# t1-power.net
KiCad netlist of a schematic drawn in Altium Designer
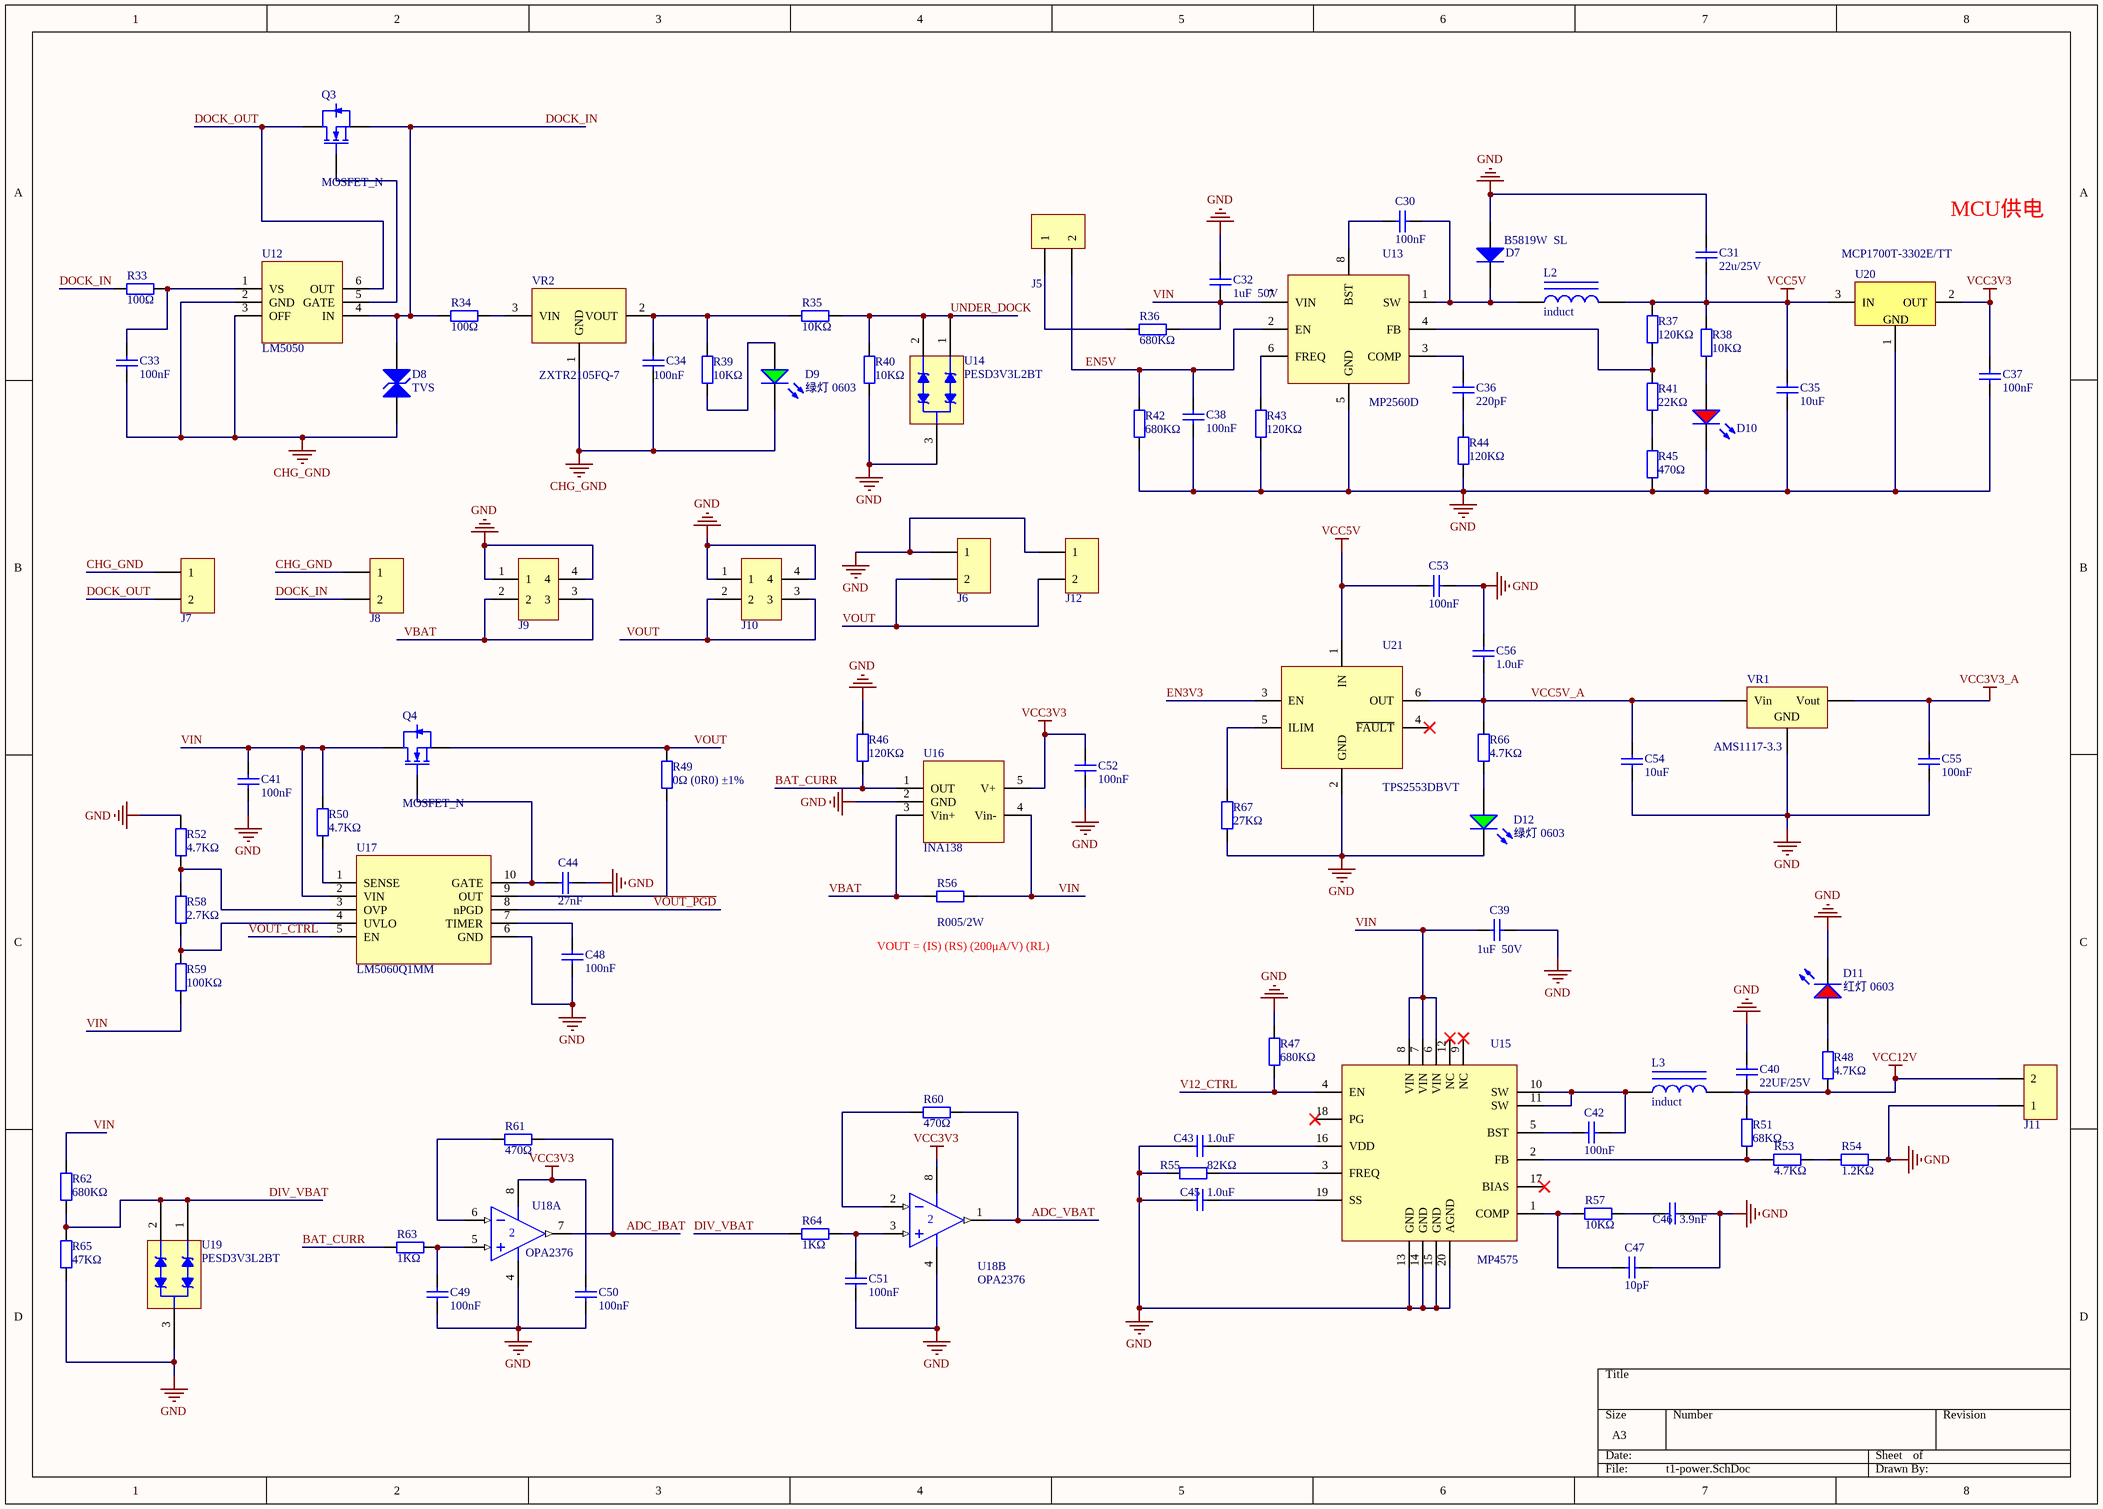
[diagram p0: t1-power.SchDoc]

(export (version "E")
  (design (tool "Eeschema 10.0.6"))
  (components
    (comp (ref "C30")
      (value "100nF")
      (footprint "0402_C")
      (description "贴片电容")
      (libsource (lib "AD封装2018.9.19Miscellaneous Devices LC") (part "0402 100nF (104) 10% 16V"))
    )
    (comp (ref "C31")
      (value "22u/25V")
      (footprint "1206_C")
      (description "贴片电容")
      (libsource (lib "AD封装2018.9.19Miscellaneous Devices LC") (part "1206 220pF (221) 10% 50V"))
    )
    (comp (ref "C32")
      (value "1uF  50V")
      (footprint "0603_C")
      (description "贴片电容")
      (libsource (lib "AD封装2018.9.19Miscellaneous Devices LC") (part "0603 1uF (105) 10% 50V"))
    )
    (comp (ref "C33")
      (value "100nF")
      (footprint "0402_C")
      (description "贴片电容")
      (libsource (lib "AD封装2018.9.19Miscellaneous Devices LC") (part "0402 100nF (104) 10% 16V"))
    )
    (comp (ref "C34")
      (value "100nF")
      (footprint "0402_C")
      (description "贴片电容")
      (libsource (lib "AD封装2018.9.19Miscellaneous Devices LC") (part "0402 100nF (104) 10% 16V"))
    )
    (comp (ref "C35")
      (value "10uF")
      (footprint "0603_C")
      (description "贴片电容")
      (libsource (lib "AD封装2018.9.19Miscellaneous Devices LC") (part "0603 10uF (106) 10% 10V"))
    )
    (comp (ref "C36")
      (value "220pF")
      (footprint "0402_C")
      (description "贴片电容")
      (libsource (lib "AD封装2018.9.19Miscellaneous Devices LC") (part "0402 220pF (221) 10% 50V"))
    )
    (comp (ref "C37")
      (value "100nF")
      (footprint "0402_C")
      (description "贴片电容")
      (libsource (lib "AD封装2018.9.19Miscellaneous Devices LC") (part "0402 100nF (104) 10% 16V"))
    )
    (comp (ref "C38")
      (value "100nF")
      (footprint "0402_C")
      (description "贴片电容")
      (libsource (lib "AD封装2018.9.19Miscellaneous Devices LC") (part "0402 100nF (104) 10% 16V"))
    )
    (comp (ref "C39")
      (value "1uF  50V")
      (footprint "1206_C")
      (description "贴片电容")
      (libsource (lib "AD封装2018.9.19Miscellaneous Devices LC") (part "1206 1uF (105) 10% 50V"))
    )
    (comp (ref "C40")
      (value "22UF/25V")
      (footprint "1206_C")
      (description "贴片电容")
      (libsource (lib "AD封装2018.9.19Miscellaneous Devices LC") (part "1206 10uF (106) 10% 50V"))
    )
    (comp (ref "C41")
      (value "100nF")
      (footprint "0402_C")
      (description "贴片电容")
      (libsource (lib "AD封装2018.9.19Miscellaneous Devices LC") (part "0402 100nF (104) 10% 16V"))
    )
    (comp (ref "C42")
      (value "100nF")
      (footprint "0402_C")
      (description "贴片电容")
      (libsource (lib "AD封装2018.9.19Miscellaneous Devices LC") (part "0402 100nF (104) 10% 16V"))
    )
    (comp (ref "C43")
      (value "1.0uF")
      (footprint "0402_C")
      (description "贴片电容")
      (libsource (lib "AD封装2018.9.19Miscellaneous Devices LC") (part "0402 1.0uF (105) 10% 25V"))
    )
    (comp (ref "C44")
      (value "27nF")
      (footprint "0402_C")
      (description "贴片电容")
      (libsource (lib "AD封装2018.9.19Miscellaneous Devices LC") (part "0402 1.0uF (105) 10% 25V"))
    )
    (comp (ref "C45")
      (value "1.0uF")
      (footprint "0402_C")
      (description "贴片电容")
      (libsource (lib "AD封装2018.9.19Miscellaneous Devices LC") (part "0402 1.0uF (105) 10% 25V"))
    )
    (comp (ref "C46")
      (value "3.9nF")
      (footprint "0402_C")
      (description "贴片电容")
      (libsource (lib "AD封装2018.9.19Miscellaneous Devices LC") (part "0402 10pF (100) 5% 50V"))
    )
    (comp (ref "C47")
      (value "10pF")
      (footprint "0402_C")
      (description "贴片电容")
      (libsource (lib "AD封装2018.9.19Miscellaneous Devices LC") (part "0402 10pF (100) 5% 50V"))
    )
    (comp (ref "C48")
      (value "100nF")
      (footprint "0402_C")
      (description "贴片电容")
      (libsource (lib "AD封装2018.9.19Miscellaneous Devices LC") (part "0402 100nF (104) 10% 16V"))
    )
    (comp (ref "C49")
      (value "100nF")
      (footprint "0402_C")
      (description "贴片电容")
      (libsource (lib "AD封装2018.9.19Miscellaneous Devices LC") (part "0402 100nF (104) 10% 16V"))
    )
    (comp (ref "C50")
      (value "100nF")
      (footprint "0402_C")
      (description "贴片电容")
      (libsource (lib "AD封装2018.9.19Miscellaneous Devices LC") (part "0402 100nF (104) 10% 16V"))
    )
    (comp (ref "C51")
      (value "100nF")
      (footprint "0402_C")
      (description "贴片电容")
      (libsource (lib "AD封装2018.9.19Miscellaneous Devices LC") (part "0402 100nF (104) 10% 16V"))
    )
    (comp (ref "C52")
      (value "100nF")
      (footprint "0402_C")
      (description "贴片电容")
      (libsource (lib "AD封装2018.9.19Miscellaneous Devices LC") (part "0402 100nF (104) 10% 16V"))
    )
    (comp (ref "C53")
      (value "100nF")
      (footprint "0402_C")
      (description "贴片电容")
      (libsource (lib "AD封装2018.9.19Miscellaneous Devices LC") (part "0402 100nF (104) 10% 16V"))
    )
    (comp (ref "C54")
      (value "10uF")
      (footprint "0603_C")
      (description "贴片电容")
      (libsource (lib "AD封装2018.9.19Miscellaneous Devices LC") (part "0603 10uF (106) 10% 10V"))
    )
    (comp (ref "C55")
      (value "100nF")
      (footprint "0402_C")
      (description "贴片电容")
      (libsource (lib "AD封装2018.9.19Miscellaneous Devices LC") (part "0402 100nF (104) 10% 16V"))
    )
    (comp (ref "C56")
      (value "1.0uF")
      (footprint "0402_C")
      (description "贴片电容")
      (libsource (lib "AD封装2018.9.19Miscellaneous Devices LC") (part "0402 1.0uF (105) 10% 25V"))
    )
    (comp (ref "D7")
      (value "B5819W  SL")
      (footprint "SOD-123")
      (description "肖特基二极管")
      (libsource (lib "Diode") (part "SOD-123 B5819W  SL"))
    )
    (comp (ref "D8") (value "TVS") (footprint "DO-214AC") (libsource (lib "我的集成库") (part "TVS")))
    (comp (ref "D9")
      (value "绿灯 0603")
      (footprint "0603_LED_S1")
      (description "发光二极管")
      (libsource (lib "AD封装2018.9.19Miscellaneous Devices LC") (part "0603 绿灯"))
    )
    (comp (ref "D10")
      (value "红灯 0603")
      (footprint "0603_LED_S1")
      (description "发光二极管")
      (libsource (lib "AD封装2018.9.19Miscellaneous Devices LC") (part "0603 红灯"))
    )
    (comp (ref "D11")
      (value "红灯 0603")
      (footprint "0603_LED_S1")
      (description "发光二极管")
      (libsource (lib "AD封装2018.9.19Miscellaneous Devices LC") (part "0603 红灯"))
    )
    (comp (ref "D12")
      (value "绿灯 0603")
      (footprint "0603_LED_S1")
      (description "发光二极管")
      (libsource (lib "AD封装2018.9.19Miscellaneous Devices LC") (part "0603 绿灯"))
    )
    (comp (ref "J5") (value "MOTOR") (footprint "KF2510-2A针座-2.54mm") (libsource (lib "") (part "header2_2")))
    (comp (ref "J6") (value "MOTOR") (footprint "5557_a") (libsource (lib "") (part "header2_1")))
    (comp (ref "J7") (value "MOTOR") (footprint "MX_3.0_2X1P") (libsource (lib "") (part "header2_1")))
    (comp (ref "J8") (value "MOTOR") (footprint "MX_3.0_2X1P") (libsource (lib "") (part "header2_1")))
    (comp (ref "J9")
      (value "HEADER_2*2P")
      (footprint "5557_2*2PA")
      (libsource (lib "我的集成库") (part "HEADER_2*2P"))
    )
    (comp (ref "J10")
      (value "HEADER_2*2P")
      (footprint "5557_2*2PA")
      (libsource (lib "我的集成库") (part "HEADER_2*2P"))
    )
    (comp (ref "J11") (value "MOTOR") (footprint "MX_3.0_2X1P") (libsource (lib "我的集成库") (part "header2")))
    (comp (ref "J12") (value "MOTOR") (footprint "5557_a") (libsource (lib "") (part "header2_1")))
    (comp (ref "L2")
      (value "induct")
      (footprint "SMD,5.0x5.0x4.0mm")
      (libsource (lib "我的原理图库") (part "induct"))
    )
    (comp (ref "L3")
      (value "induct")
      (footprint "SMD,5.0x5.0x4.0mm")
      (libsource (lib "我的原理图库") (part "induct"))
    )
    (comp (ref "Q3") (value "MOSFET_N") (footprint "TO-252-2") (libsource (lib "我的原理图库") (part "MOSFET_N")))
    (comp (ref "Q4") (value "MOSFET_N") (footprint "T0-263-2") (libsource (lib "我的原理图库") (part "MOSFET_N")))
    (comp (ref "R33")
      (value "100Ω")
      (footprint "0402_R")
      (description "贴片电阻")
      (libsource (lib "AD封装2018.9.19Miscellaneous Devices LC") (part "0402 100Ω (1000) 1%"))
    )
    (comp (ref "R34")
      (value "100Ω")
      (footprint "0402_R")
      (description "贴片电阻")
      (libsource (lib "AD封装2018.9.19Miscellaneous Devices LC") (part "0402 100Ω (1000) 1%"))
    )
    (comp (ref "R35")
      (value "10KΩ")
      (footprint "0402_R")
      (description "贴片电阻")
      (libsource (lib "") (part "0402 10KΩ (1002) 1%_2"))
    )
    (comp (ref "R36")
      (value "680KΩ")
      (footprint "0402_R")
      (description "贴片电阻")
      (libsource (lib "AD封装2018.9.19Miscellaneous Devices LC") (part "0402 680Ω (6800) 1%"))
    )
    (comp (ref "R37")
      (value "120KΩ")
      (footprint "0402_R")
      (description "贴片电阻")
      (libsource (lib "AD封装2018.9.19Miscellaneous Devices LC") (part "0402 10KΩ (1002) 1%"))
    )
    (comp (ref "R38")
      (value "10KΩ")
      (footprint "0402_R")
      (description "贴片电阻")
      (libsource (lib "AD封装2018.9.19Miscellaneous Devices LC") (part "0402 10KΩ (1002) 1%"))
    )
    (comp (ref "R39")
      (value "10KΩ")
      (footprint "0402_R")
      (description "贴片电阻")
      (libsource (lib "AD封装2018.9.19Miscellaneous Devices LC") (part "0402 10KΩ (1002) 1%"))
    )
    (comp (ref "R40")
      (value "10KΩ")
      (footprint "0402_R")
      (description "贴片电阻")
      (libsource (lib "") (part "0402 10KΩ (1002) 1%_1"))
    )
    (comp (ref "R41")
      (value "22KΩ")
      (footprint "0402_R")
      (description "贴片电阻")
      (libsource (lib "AD封装2018.9.19Miscellaneous Devices LC") (part "0402 22KΩ (2202) 1%"))
    )
    (comp (ref "R42")
      (value "680KΩ")
      (footprint "0402_R")
      (description "贴片电阻")
      (libsource (lib "") (part "0402 680Ω (6800) 1%_1"))
    )
    (comp (ref "R43")
      (value "120KΩ")
      (footprint "0402_R")
      (description "贴片电阻")
      (libsource (lib "AD封装2018.9.19Miscellaneous Devices LC") (part "0402 120KΩ (1203) 1%"))
    )
    (comp (ref "R44")
      (value "120KΩ")
      (footprint "0402_R")
      (description "贴片电阻")
      (libsource (lib "AD封装2018.9.19Miscellaneous Devices LC") (part "0402 120KΩ (1203) 1%"))
    )
    (comp (ref "R45")
      (value "470Ω")
      (footprint "0402_R")
      (description "贴片电阻")
      (libsource (lib "") (part "0402 470Ω (4700) 1%_1"))
    )
    (comp (ref "R46")
      (value "120KΩ")
      (footprint "0402_R")
      (description "贴片电阻")
      (libsource (lib "AD封装2018.9.19Miscellaneous Devices LC") (part "0402 120KΩ (1203) 1%"))
    )
    (comp (ref "R47")
      (value "680KΩ")
      (footprint "0402_R")
      (description "贴片电阻")
      (libsource (lib "") (part "0402 680Ω (6800) 1%_1"))
    )
    (comp (ref "R48")
      (value "4.7KΩ")
      (footprint "0402_R")
      (description "贴片电阻")
      (libsource (lib "AD封装2018.9.19Miscellaneous Devices LC") (part "0402 47KΩ (4702) 1%"))
    )
    (comp (ref "R49")
      (value "0Ω (0R0) ±1%")
      (footprint "0402_R")
      (description "贴片电阻")
      (libsource (lib "AD封装2018.9.19Miscellaneous Devices LC") (part "0402 0Ω (0R0) 1%"))
    )
    (comp (ref "R50")
      (value "4.7KΩ")
      (footprint "0402_R")
      (description "贴片电阻")
      (libsource (lib "") (part "0402 4.7KΩ (4701) 1%_2"))
    )
    (comp (ref "R51")
      (value "68KΩ")
      (footprint "0402_R")
      (description "贴片电阻")
      (libsource (lib "AD封装2018.9.19Miscellaneous Devices LC") (part "0402 68KΩ (6802) 1%"))
    )
    (comp (ref "R52")
      (value "4.7KΩ")
      (footprint "0402_R")
      (description "贴片电阻")
      (libsource (lib "") (part "0402 4.7KΩ (4701) 1%_1"))
    )
    (comp (ref "R53")
      (value "4.7KΩ")
      (footprint "0402_R")
      (description "贴片电阻")
      (libsource (lib "AD封装2018.9.19Miscellaneous Devices LC") (part "0402 4.7KΩ (4701) 1%"))
    )
    (comp (ref "R54")
      (value "1.2KΩ")
      (footprint "0402_R")
      (description "贴片电阻")
      (libsource (lib "AD封装2018.9.19Miscellaneous Devices LC") (part "0402 1.2KΩ (1201) 1%"))
    )
    (comp (ref "R55")
      (value "82KΩ")
      (footprint "0402_R")
      (description "贴片电阻")
      (libsource (lib "AD封装2018.9.19Miscellaneous Devices LC") (part "0402 680Ω (6800) 1%"))
    )
    (comp (ref "R56") (value "R005/2W") (footprint "2512") (libsource (lib "我的集成库") (part "RES")))
    (comp (ref "R57")
      (value "10KΩ")
      (footprint "0402_R")
      (description "贴片电阻")
      (libsource (lib "") (part "0402 10KΩ (1002) 1%_3"))
    )
    (comp (ref "R58")
      (value "2.7KΩ")
      (footprint "0402_R")
      (description "贴片电阻")
      (libsource (lib "") (part "0402 4.7KΩ (4701) 1%_1"))
    )
    (comp (ref "R59")
      (value "100KΩ")
      (footprint "0402_R")
      (description "贴片电阻")
      (libsource (lib "AD封装2018.9.19Miscellaneous Devices LC") (part "0402 100KΩ (1003) 1%"))
    )
    (comp (ref "R60")
      (value "470Ω")
      (footprint "0402_R")
      (description "贴片电阻")
      (libsource (lib "AD封装2018.9.19Miscellaneous Devices LC") (part "0402 470Ω (4700) 1%"))
    )
    (comp (ref "R61")
      (value "470Ω")
      (footprint "0402_R")
      (description "贴片电阻")
      (libsource (lib "AD封装2018.9.19Miscellaneous Devices LC") (part "0402 470Ω (4700) 1%"))
    )
    (comp (ref "R62")
      (value "680KΩ")
      (footprint "0402_R")
      (description "贴片电阻")
      (libsource (lib "") (part "0402 680Ω (6800) 1%_1"))
    )
    (comp (ref "R63")
      (value "1KΩ")
      (footprint "0402_R")
      (description "贴片电阻")
      (libsource (lib "AD封装2018.9.19Miscellaneous Devices LC") (part "0402 1KΩ (1001) 1%"))
    )
    (comp (ref "R64")
      (value "1KΩ")
      (footprint "0402_R")
      (description "贴片电阻")
      (libsource (lib "AD封装2018.9.19Miscellaneous Devices LC") (part "0402 1KΩ (1001) 1%"))
    )
    (comp (ref "R65")
      (value "47KΩ")
      (footprint "0402_R")
      (description "贴片电阻")
      (libsource (lib "AD封装2018.9.19Miscellaneous Devices LC") (part "0402 47KΩ (4702) 1%"))
    )
    (comp (ref "R66")
      (value "4.7KΩ")
      (footprint "0402_R")
      (description "贴片电阻")
      (libsource (lib "") (part "0402 4.7KΩ (4701) 1%_2"))
    )
    (comp (ref "R67")
      (value "27KΩ")
      (footprint "0402_R")
      (description "贴片电阻")
      (libsource (lib "AD封装2018.9.19Miscellaneous Devices LC") (part "0402 27KΩ (2702) 1%"))
    )
    (comp (ref "U12") (value "LM5050") (footprint "TSOT-23-6") (libsource (lib "我的集成库") (part "LM5050")))
    (comp (ref "U13")
      (value "MP2560D")
      (footprint "SOP-8_150mil")
      (description "MP2560D_SOIC-8_EP_150mil")
      (libsource (lib "我的集成库") (part "MP2560D"))
    )
    (comp (ref "U14")
      (value "PESD3V3L2BT")
      (footprint "SOT-23(SOT-23-3)")
      (description "TVS")
      (libsource (lib "AD封装2018.9.19Miscellaneous Devices LC") (part "PSM712-LF-T7_[C32677]"))
    )
    (comp (ref "U15")
      (value "MP4575")
      (footprint "TSSOP-20")
      (description "MP4575_TSSOP-20")
      (libsource (lib "我的集成库") (part "MP4575"))
    )
    (comp (ref "U16")
      (value "INA138")
      (footprint "SOT-23-5")
      (description "SOT-23-5")
      (libsource (lib "我的集成库") (part "INA138"))
    )
    (comp (ref "U17")
      (value "LM5060Q1MM")
      (footprint "VSSOP-10")
      (libsource (lib "我的集成库") (part "LM5060Q1MM"))
    )
    (comp (ref "U18")
      (value "OPA2376")
      (footprint "SOP-8_150mil")
      (description "精密运放")
      (libsource (lib "我的集成库") (part "OPA2376"))
    )
    (comp (ref "U19")
      (value "PESD3V3L2BT")
      (footprint "SOT-23(SOT-23-3)")
      (description "TVS")
      (libsource (lib "AD封装2018.9.19Miscellaneous Devices LC") (part "PSM712-LF-T7_[C32677]"))
    )
    (comp (ref "U20")
      (value "MCP1700T-3302E/TT")
      (footprint "SOT-23-3")
      (description "https://item.szlcsc.com/40034.html LDO 3.3V")
      (libsource (lib "我的集成库") (part "MCP1700T-3302E/TT LDO 3.3V"))
    )
    (comp (ref "U21")
      (value "TPS2553DBVT")
      (footprint "SOT-23-6")
      (description "SOT-23-6")
      (libsource (lib "我的集成库") (part "TPS2553DBVT"))
    )
    (comp (ref "VR1")
      (value "AMS1117-3.3")
      (footprint "SOT-223")
      (description "低压差线性稳压(LDO)")
      (libsource (lib "LDO") (part "SOT-223 AMS1117-3.3"))
    )
    (comp (ref "VR2")
      (value "ZXTR2105FQ-7")
      (footprint "SOT-23-3")
      (description "线性稳压芯片 60V 89ma")
      (libsource (lib "我的集成库") (part "ZXTR2105FQ-7"))
    )
  )
  (nets
    (net (code "1") (name "/ADC_IBAT") (class "Default")
      (node (ref "R61") (pin "2") (pinfunction "2_2") (pintype "passive"))
      (node (ref "U18") (pin "7") (pinfunction "OUT_7") (pintype "output"))
    )
    (net (code "2") (name "/ADC_VBAT") (class "Default")
      (node (ref "R60") (pin "2") (pinfunction "2_2") (pintype "passive"))
      (node (ref "U18") (pin "1") (pinfunction "OUT_1") (pintype "output"))
    )
    (net (code "3") (name "/BAT_CURR") (class "Default")
      (node (ref "R46") (pin "1") (pinfunction "1_1") (pintype "passive"))
      (node (ref "R63") (pin "1") (pinfunction "1_1") (pintype "passive"))
      (node (ref "U16") (pin "1") (pinfunction "OUT_1") (pintype "passive"))
    )
    (net (code "4") (name "/DIV_VBAT") (class "Default")
      (node (ref "R62") (pin "1") (pinfunction "1_1") (pintype "passive"))
      (node (ref "R64") (pin "1") (pinfunction "1_1") (pintype "passive"))
      (node (ref "R65") (pin "2") (pinfunction "2_2") (pintype "passive"))
      (node (ref "U19") (pin "1") (pinfunction "1_1") (pintype "passive"))
      (node (ref "U19") (pin "2") (pinfunction "2_2") (pintype "passive"))
    )
    (net (code "5") (name "/DOCK_IN") (class "Default")
      (node (ref "D8") (pin "2") (pinfunction "K_2") (pintype "passive"))
      (node (ref "J8") (pin "2") (pinfunction "2_2") (pintype "passive"))
      (node (ref "Q3") (pin "3") (pinfunction "S_3") (pintype "passive"))
      (node (ref "R33") (pin "1") (pinfunction "1_1") (pintype "passive"))
      (node (ref "R34") (pin "1") (pinfunction "1_1") (pintype "passive"))
      (node (ref "U12") (pin "4") (pinfunction "IN_4") (pintype "passive"))
    )
    (net (code "6") (name "/DOCK_OUT") (class "Default")
      (node (ref "J7") (pin "2") (pinfunction "2_2") (pintype "passive"))
      (node (ref "Q3") (pin "2") (pinfunction "D_2") (pintype "passive"))
      (node (ref "U12") (pin "6") (pinfunction "OUT_6") (pintype "passive"))
    )
    (net (code "7") (name "/EN3V3") (class "Default")
      (node (ref "U21") (pin "3") (pinfunction "EN_3") (pintype "passive"))
    )
    (net (code "8") (name "/EN5V") (class "Default")
      (node (ref "C38") (pin "2") (pinfunction "2_2") (pintype "passive"))
      (node (ref "J5") (pin "2") (pinfunction "2_2") (pintype "passive"))
      (node (ref "R42") (pin "2") (pinfunction "2_2") (pintype "passive"))
      (node (ref "U13") (pin "2") (pinfunction "EN_2") (pintype "passive"))
    )
    (net (code "9") (name "/UNDER_DOCK") (class "Default")
      (node (ref "R35") (pin "1") (pinfunction "1_1") (pintype "passive"))
      (node (ref "R40") (pin "1") (pinfunction "1_1") (pintype "passive"))
      (node (ref "U14") (pin "1") (pinfunction "1_1") (pintype "passive"))
      (node (ref "U14") (pin "2") (pinfunction "2_2") (pintype "passive"))
    )
    (net (code "10") (name "/V12_CTRL") (class "Default")
      (node (ref "R47") (pin "1") (pinfunction "1_1") (pintype "passive"))
      (node (ref "U15") (pin "4") (pinfunction "EN_4") (pintype "passive"))
    )
    (net (code "11") (name "/VBAT") (class "Default")
      (node (ref "J9") (pin "2") (pinfunction "2_2") (pintype "passive"))
      (node (ref "J9") (pin "3") (pinfunction "3_3") (pintype "passive"))
      (node (ref "R56") (pin "1") (pinfunction "1_1") (pintype "passive"))
      (node (ref "U16") (pin "3") (pinfunction "Vin+_3") (pintype "passive"))
    )
    (net (code "12") (name "/VCC5V_A") (class "Default")
      (node (ref "C54") (pin "2") (pinfunction "2_2") (pintype "passive"))
      (node (ref "C56") (pin "1") (pinfunction "1_1") (pintype "passive"))
      (node (ref "R66") (pin "2") (pinfunction "2_2") (pintype "passive"))
      (node (ref "U21") (pin "6") (pinfunction "OUT_6") (pintype "passive"))
      (node (ref "VR1") (pin "3") (pinfunction "Vin_3") (pintype "passive"))
    )
    (net (code "13") (name "/VIN") (class "Default")
      (node (ref "C32") (pin "1") (pinfunction "1_1") (pintype "passive"))
      (node (ref "C39") (pin "1") (pinfunction "1_1") (pintype "passive"))
      (node (ref "C41") (pin "2") (pinfunction "2_2") (pintype "passive"))
      (node (ref "Q4") (pin "2") (pinfunction "D_2") (pintype "passive"))
      (node (ref "R36") (pin "2") (pinfunction "2_2") (pintype "passive"))
      (node (ref "R50") (pin "2") (pinfunction "2_2") (pintype "passive"))
      (node (ref "R56") (pin "2") (pinfunction "2_2") (pintype "passive"))
      (node (ref "R59") (pin "2") (pinfunction "2_2") (pintype "passive"))
      (node (ref "R62") (pin "2") (pinfunction "2_2") (pintype "passive"))
      (node (ref "U13") (pin "7") (pinfunction "VIN_7") (pintype "passive"))
      (node (ref "U15") (pin "6") (pinfunction "VIN_6") (pintype "passive"))
      (node (ref "U15") (pin "7") (pinfunction "VIN_7") (pintype "passive"))
      (node (ref "U15") (pin "8") (pinfunction "VIN_8") (pintype "passive"))
      (node (ref "U16") (pin "4") (pinfunction "Vin-_4") (pintype "passive"))
      (node (ref "U17") (pin "2") (pinfunction "VIN_2") (pintype "passive"))
    )
    (net (code "14") (name "/VOUT") (class "Default")
      (node (ref "J10") (pin "2") (pinfunction "2_2") (pintype "passive"))
      (node (ref "J10") (pin "3") (pinfunction "3_3") (pintype "passive"))
      (node (ref "J12") (pin "2") (pinfunction "2_2") (pintype "passive"))
      (node (ref "J6") (pin "2") (pinfunction "2_2") (pintype "passive"))
      (node (ref "Q4") (pin "3") (pinfunction "S_3") (pintype "passive"))
      (node (ref "R49") (pin "2") (pinfunction "2_2") (pintype "passive"))
    )
    (net (code "15") (name "/VOUT_CTRL") (class "Default")
      (node (ref "U17") (pin "5") (pinfunction "EN_5") (pintype "passive"))
    )
    (net (code "16") (name "/~{VOUT_PGD}") (class "Default")
      (node (ref "U17") (pin "8") (pinfunction "nPGD_8") (pintype "passive"))
    )
    (net (code "17") (name "CHG_GND") (class "Default")
      (node (ref "C33") (pin "1") (pinfunction "1_1") (pintype "passive"))
      (node (ref "C34") (pin "1") (pinfunction "1_1") (pintype "passive"))
      (node (ref "D8") (pin "1") (pinfunction "A_1") (pintype "passive"))
      (node (ref "D9") (pin "K") (pinfunction "K_K") (pintype "passive"))
      (node (ref "J7") (pin "1") (pinfunction "1_1") (pintype "passive"))
      (node (ref "J8") (pin "1") (pinfunction "1_1") (pintype "passive"))
      (node (ref "U12") (pin "2") (pinfunction "GND_2") (pintype "passive"))
      (node (ref "U12") (pin "3") (pinfunction "OFF_3") (pintype "passive"))
      (node (ref "VR2") (pin "1") (pinfunction "GND_1") (pintype "passive"))
    )
    (net (code "18") (name "GND") (class "Default")
      (node (ref "C31") (pin "2") (pinfunction "2_2") (pintype "passive"))
      (node (ref "C32") (pin "2") (pinfunction "2_2") (pintype "passive"))
      (node (ref "C35") (pin "1") (pinfunction "1_1") (pintype "passive"))
      (node (ref "C37") (pin "1") (pinfunction "1_1") (pintype "passive"))
      (node (ref "C38") (pin "1") (pinfunction "1_1") (pintype "passive"))
      (node (ref "C39") (pin "2") (pinfunction "2_2") (pintype "passive"))
      (node (ref "C40") (pin "2") (pinfunction "2_2") (pintype "passive"))
      (node (ref "C41") (pin "1") (pinfunction "1_1") (pintype "passive"))
      (node (ref "C43") (pin "2") (pinfunction "2_2") (pintype "passive"))
      (node (ref "C44") (pin "2") (pinfunction "2_2") (pintype "passive"))
      (node (ref "C45") (pin "2") (pinfunction "2_2") (pintype "passive"))
      (node (ref "C46") (pin "2") (pinfunction "2_2") (pintype "passive"))
      (node (ref "C47") (pin "2") (pinfunction "2_2") (pintype "passive"))
      (node (ref "C48") (pin "2") (pinfunction "2_2") (pintype "passive"))
      (node (ref "C49") (pin "1") (pinfunction "1_1") (pintype "passive"))
      (node (ref "C50") (pin "1") (pinfunction "1_1") (pintype "passive"))
      (node (ref "C51") (pin "2") (pinfunction "2_2") (pintype "passive"))
      (node (ref "C52") (pin "2") (pinfunction "2_2") (pintype "passive"))
      (node (ref "C53") (pin "2") (pinfunction "2_2") (pintype "passive"))
      (node (ref "C54") (pin "1") (pinfunction "1_1") (pintype "passive"))
      (node (ref "C55") (pin "1") (pinfunction "1_1") (pintype "passive"))
      (node (ref "C56") (pin "2") (pinfunction "2_2") (pintype "passive"))
      (node (ref "D10") (pin "K") (pinfunction "K_K") (pintype "passive"))
      (node (ref "D11") (pin "K") (pinfunction "K_K") (pintype "passive"))
      (node (ref "D12") (pin "K") (pinfunction "K_K") (pintype "passive"))
      (node (ref "D7") (pin "1") (pinfunction "A_1") (pintype "passive"))
      (node (ref "J10") (pin "1") (pinfunction "1_1") (pintype "passive"))
      (node (ref "J10") (pin "4") (pinfunction "4_4") (pintype "passive"))
      (node (ref "J11") (pin "1") (pinfunction "1_1") (pintype "passive"))
      (node (ref "J12") (pin "1") (pinfunction "1_1") (pintype "passive"))
      (node (ref "J6") (pin "1") (pinfunction "1_1") (pintype "passive"))
      (node (ref "J9") (pin "1") (pinfunction "1_1") (pintype "passive"))
      (node (ref "J9") (pin "4") (pinfunction "4_4") (pintype "passive"))
      (node (ref "R40") (pin "2") (pinfunction "2_2") (pintype "passive"))
      (node (ref "R42") (pin "1") (pinfunction "1_1") (pintype "passive"))
      (node (ref "R43") (pin "1") (pinfunction "1_1") (pintype "passive"))
      (node (ref "R44") (pin "1") (pinfunction "1_1") (pintype "passive"))
      (node (ref "R45") (pin "1") (pinfunction "1_1") (pintype "passive"))
      (node (ref "R46") (pin "2") (pinfunction "2_2") (pintype "passive"))
      (node (ref "R47") (pin "2") (pinfunction "2_2") (pintype "passive"))
      (node (ref "R52") (pin "1") (pinfunction "1_1") (pintype "passive"))
      (node (ref "R54") (pin "2") (pinfunction "2_2") (pintype "passive"))
      (node (ref "R55") (pin "1") (pinfunction "1_1") (pintype "passive"))
      (node (ref "R65") (pin "1") (pinfunction "1_1") (pintype "passive"))
      (node (ref "R67") (pin "1") (pinfunction "1_1") (pintype "passive"))
      (node (ref "U13") (pin "5") (pinfunction "GND_5") (pintype "passive"))
      (node (ref "U14") (pin "3") (pinfunction "3_3") (pintype "passive"))
      (node (ref "U15") (pin "13") (pinfunction "GND_13") (pintype "passive"))
      (node (ref "U15") (pin "14") (pinfunction "GND_14") (pintype "passive"))
      (node (ref "U15") (pin "15") (pinfunction "GND_15") (pintype "passive"))
      (node (ref "U15") (pin "20") (pinfunction "AGND_20") (pintype "passive"))
      (node (ref "U16") (pin "2") (pinfunction "GND_2") (pintype "passive"))
      (node (ref "U17") (pin "6") (pinfunction "GND_6") (pintype "passive"))
      (node (ref "U18") (pin "4") (pinfunction "V-_4") (pintype "power_in"))
      (node (ref "U19") (pin "3") (pinfunction "3_3") (pintype "passive"))
      (node (ref "U20") (pin "1") (pintype "passive"))
      (node (ref "U21") (pin "2") (pinfunction "GND_2") (pintype "passive"))
      (node (ref "VR1") (pin "1") (pinfunction "GND_1") (pintype "passive"))
    )
    (net (code "19") (name "Net-(C36-Pad1)") (class "Default")
      (node (ref "C36") (pin "1") (pinfunction "1_1") (pintype "passive"))
      (node (ref "R44") (pin "2") (pinfunction "2_2") (pintype "passive"))
    )
    (net (code "20") (name "Net-(C42-Pad1)") (class "Default")
      (node (ref "C42") (pin "1") (pinfunction "1_1") (pintype "passive"))
      (node (ref "L3") (pin "1") (pinfunction "1_1") (pintype "passive"))
      (node (ref "U15") (pin "10") (pinfunction "SW_10") (pintype "passive"))
      (node (ref "U15") (pin "11") (pinfunction "SW_11") (pintype "passive"))
    )
    (net (code "21") (name "Net-(C46-Pad1)") (class "Default")
      (node (ref "C46") (pin "1") (pinfunction "1_1") (pintype "passive"))
      (node (ref "R57") (pin "2") (pinfunction "2_2") (pintype "passive"))
    )
    (net (code "22") (name "Net-(D7-K)") (class "Default")
      (node (ref "C30") (pin "1") (pinfunction "1_1") (pintype "passive"))
      (node (ref "D7") (pin "2") (pinfunction "K_2") (pintype "passive"))
      (node (ref "L2") (pin "1") (pinfunction "1_1") (pintype "passive"))
      (node (ref "U13") (pin "1") (pinfunction "SW_1") (pintype "passive"))
    )
    (net (code "23") (name "Net-(D9-PadA)") (class "Default")
      (node (ref "D9") (pin "A") (pinfunction "A_A") (pintype "passive"))
      (node (ref "R39") (pin "1") (pinfunction "1_1") (pintype "passive"))
    )
    (net (code "24") (name "Net-(D10-PadA)") (class "Default")
      (node (ref "D10") (pin "A") (pinfunction "A_A") (pintype "passive"))
      (node (ref "R38") (pin "1") (pinfunction "1_1") (pintype "passive"))
    )
    (net (code "25") (name "Net-(D11-PadA)") (class "Default")
      (node (ref "D11") (pin "A") (pinfunction "A_A") (pintype "passive"))
      (node (ref "R48") (pin "2") (pinfunction "2_2") (pintype "passive"))
    )
    (net (code "26") (name "Net-(D12-PadA)") (class "Default")
      (node (ref "D12") (pin "A") (pinfunction "A_A") (pintype "passive"))
      (node (ref "R66") (pin "1") (pinfunction "1_1") (pintype "passive"))
    )
    (net (code "27") (name "Net-(J5-Pad1)") (class "Default")
      (node (ref "J5") (pin "1") (pinfunction "1_1") (pintype "passive"))
      (node (ref "R36") (pin "1") (pinfunction "1_1") (pintype "passive"))
    )
    (net (code "28") (name "Net-(Q3-G)") (class "Default")
      (node (ref "Q3") (pin "1") (pinfunction "G_1") (pintype "passive"))
      (node (ref "U12") (pin "5") (pinfunction "GATE_5") (pintype "passive"))
    )
    (net (code "29") (name "Net-(Q4-G)") (class "Default")
      (node (ref "C44") (pin "1") (pinfunction "1_1") (pintype "passive"))
      (node (ref "Q4") (pin "1") (pinfunction "G_1") (pintype "passive"))
      (node (ref "U17") (pin "10") (pinfunction "GATE_10") (pintype "passive"))
    )
    (net (code "30") (name "Net-(R41-Pad1)") (class "Default")
      (node (ref "R41") (pin "1") (pinfunction "1_1") (pintype "passive"))
      (node (ref "R45") (pin "2") (pinfunction "2_2") (pintype "passive"))
    )
    (net (code "31") (name "Net-(R53-Pad2)") (class "Default")
      (node (ref "R53") (pin "2") (pinfunction "2_2") (pintype "passive"))
      (node (ref "R54") (pin "1") (pinfunction "1_1") (pintype "passive"))
    )
    (net (code "32") (name "Net-(U12-VS)") (class "Default")
      (node (ref "C33") (pin "2") (pinfunction "2_2") (pintype "passive"))
      (node (ref "R33") (pin "2") (pinfunction "2_2") (pintype "passive"))
      (node (ref "U12") (pin "1") (pinfunction "VS_1") (pintype "passive"))
    )
    (net (code "33") (name "Net-(U13-BST)") (class "Default")
      (node (ref "C30") (pin "2") (pinfunction "2_2") (pintype "passive"))
      (node (ref "U13") (pin "8") (pinfunction "BST_8") (pintype "passive"))
    )
    (net (code "34") (name "Net-(U13-COMP)") (class "Default")
      (node (ref "C36") (pin "2") (pinfunction "2_2") (pintype "passive"))
      (node (ref "U13") (pin "3") (pinfunction "COMP_3") (pintype "passive"))
    )
    (net (code "35") (name "Net-(U13-FB)") (class "Default")
      (node (ref "R37") (pin "1") (pinfunction "1_1") (pintype "passive"))
      (node (ref "R41") (pin "2") (pinfunction "2_2") (pintype "passive"))
      (node (ref "U13") (pin "4") (pinfunction "FB_4") (pintype "passive"))
    )
    (net (code "36") (name "Net-(U13-FREQ)") (class "Default")
      (node (ref "R43") (pin "2") (pinfunction "2_2") (pintype "passive"))
      (node (ref "U13") (pin "6") (pinfunction "FREQ_6") (pintype "passive"))
    )
    (net (code "37") (name "Net-(U15-BST)") (class "Default")
      (node (ref "C42") (pin "2") (pinfunction "2_2") (pintype "passive"))
      (node (ref "U15") (pin "5") (pinfunction "BST_5") (pintype "passive"))
    )
    (net (code "38") (name "Net-(U15-COMP)") (class "Default")
      (node (ref "C47") (pin "1") (pinfunction "1_1") (pintype "passive"))
      (node (ref "R57") (pin "1") (pinfunction "1_1") (pintype "passive"))
      (node (ref "U15") (pin "1") (pinfunction "COMP_1") (pintype "passive"))
    )
    (net (code "39") (name "Net-(U15-FB)") (class "Default")
      (node (ref "R51") (pin "1") (pinfunction "1_1") (pintype "passive"))
      (node (ref "R53") (pin "1") (pinfunction "1_1") (pintype "passive"))
      (node (ref "U15") (pin "2") (pinfunction "FB_2") (pintype "passive"))
    )
    (net (code "40") (name "Net-(U15-FREQ)") (class "Default")
      (node (ref "R55") (pin "2") (pinfunction "2_2") (pintype "passive"))
      (node (ref "U15") (pin "3") (pinfunction "FREQ_3") (pintype "passive"))
    )
    (net (code "41") (name "Net-(U15-SS)") (class "Default")
      (node (ref "C45") (pin "1") (pinfunction "1_1") (pintype "passive"))
      (node (ref "U15") (pin "19") (pinfunction "SS_19") (pintype "passive"))
    )
    (net (code "42") (name "Net-(U15-VDD)") (class "Default")
      (node (ref "C43") (pin "1") (pinfunction "1_1") (pintype "passive"))
      (node (ref "U15") (pin "16") (pinfunction "VDD_16") (pintype "passive"))
    )
    (net (code "43") (name "Net-(U17-OUT)") (class "Default")
      (node (ref "R49") (pin "1") (pinfunction "1_1") (pintype "passive"))
      (node (ref "U17") (pin "9") (pinfunction "OUT_9") (pintype "passive"))
    )
    (net (code "44") (name "Net-(U17-OVP)") (class "Default")
      (node (ref "R52") (pin "2") (pinfunction "2_2") (pintype "passive"))
      (node (ref "R58") (pin "1") (pinfunction "1_1") (pintype "passive"))
      (node (ref "U17") (pin "3") (pinfunction "OVP_3") (pintype "passive"))
    )
    (net (code "45") (name "Net-(U17-SENSE)") (class "Default")
      (node (ref "R50") (pin "1") (pinfunction "1_1") (pintype "passive"))
      (node (ref "U17") (pin "1") (pinfunction "SENSE_1") (pintype "passive"))
    )
    (net (code "46") (name "Net-(U17-TIMER)") (class "Default")
      (node (ref "C48") (pin "1") (pinfunction "1_1") (pintype "passive"))
      (node (ref "U17") (pin "7") (pinfunction "TIMER_7") (pintype "passive"))
    )
    (net (code "47") (name "Net-(U17-UVLO)") (class "Default")
      (node (ref "R58") (pin "2") (pinfunction "2_2") (pintype "passive"))
      (node (ref "R59") (pin "1") (pinfunction "1_1") (pintype "passive"))
      (node (ref "U17") (pin "4") (pinfunction "UVLO_4") (pintype "passive"))
    )
    (net (code "48") (name "Net-(U18A-IN+)") (class "Default")
      (node (ref "C49") (pin "2") (pinfunction "2_2") (pintype "passive"))
      (node (ref "R63") (pin "2") (pinfunction "2_2") (pintype "passive"))
      (node (ref "U18") (pin "5") (pinfunction "IN+_5") (pintype "input"))
    )
    (net (code "49") (name "Net-(U18A-IN-)") (class "Default")
      (node (ref "R61") (pin "1") (pinfunction "1_1") (pintype "passive"))
      (node (ref "U18") (pin "6") (pinfunction "IN-_6") (pintype "input"))
    )
    (net (code "50") (name "Net-(U18B-IN+)") (class "Default")
      (node (ref "C51") (pin "1") (pinfunction "1_1") (pintype "passive"))
      (node (ref "R64") (pin "2") (pinfunction "2_2") (pintype "passive"))
      (node (ref "U18") (pin "3") (pinfunction "IN+_3") (pintype "input"))
    )
    (net (code "51") (name "Net-(U18B-IN-)") (class "Default")
      (node (ref "R60") (pin "1") (pinfunction "1_1") (pintype "passive"))
      (node (ref "U18") (pin "2") (pinfunction "IN-_2") (pintype "input"))
    )
    (net (code "52") (name "Net-(U21-ILIM)") (class "Default")
      (node (ref "R67") (pin "2") (pinfunction "2_2") (pintype "passive"))
      (node (ref "U21") (pin "5") (pinfunction "ILIM_5") (pintype "passive"))
    )
    (net (code "53") (name "Net-(VR2-VIN)") (class "Default")
      (node (ref "R34") (pin "2") (pinfunction "2_2") (pintype "passive"))
      (node (ref "VR2") (pin "3") (pinfunction "VIN_3") (pintype "passive"))
    )
    (net (code "54") (name "Net-(VR2-VOUT)") (class "Default")
      (node (ref "C34") (pin "2") (pinfunction "2_2") (pintype "passive"))
      (node (ref "R35") (pin "2") (pinfunction "2_2") (pintype "passive"))
      (node (ref "R39") (pin "2") (pinfunction "2_2") (pintype "passive"))
      (node (ref "VR2") (pin "2") (pinfunction "VOUT_2") (pintype "passive"))
    )
    (net (code "55") (name "VCC3V3") (class "Default")
      (node (ref "C37") (pin "2") (pinfunction "2_2") (pintype "passive"))
      (node (ref "C50") (pin "2") (pinfunction "2_2") (pintype "passive"))
      (node (ref "C52") (pin "1") (pinfunction "1_1") (pintype "passive"))
      (node (ref "U16") (pin "5") (pinfunction "V+_5") (pintype "passive"))
      (node (ref "U18") (pin "8") (pinfunction "V+_8") (pintype "power_in"))
      (node (ref "U20") (pin "2") (pinfunction "OUT_2") (pintype "passive"))
    )
    (net (code "56") (name "VCC3V3_A") (class "Default")
      (node (ref "C55") (pin "2") (pinfunction "2_2") (pintype "passive"))
      (node (ref "VR1") (pin "2") (pinfunction "Vout_2") (pintype "passive"))
    )
    (net (code "57") (name "VCC5V") (class "Default")
      (node (ref "C31") (pin "1") (pinfunction "1_1") (pintype "passive"))
      (node (ref "C35") (pin "2") (pinfunction "2_2") (pintype "passive"))
      (node (ref "C53") (pin "1") (pinfunction "1_1") (pintype "passive"))
      (node (ref "L2") (pin "2") (pinfunction "2_2") (pintype "passive"))
      (node (ref "R37") (pin "2") (pinfunction "2_2") (pintype "passive"))
      (node (ref "R38") (pin "2") (pinfunction "2_2") (pintype "passive"))
      (node (ref "U20") (pin "3") (pinfunction "IN_3") (pintype "passive"))
      (node (ref "U21") (pin "1") (pinfunction "IN_1") (pintype "passive"))
    )
    (net (code "58") (name "VCC12V") (class "Default")
      (node (ref "C40") (pin "1") (pinfunction "1_1") (pintype "passive"))
      (node (ref "J11") (pin "2") (pinfunction "2_2") (pintype "passive"))
      (node (ref "L3") (pin "2") (pinfunction "2_2") (pintype "passive"))
      (node (ref "R48") (pin "1") (pinfunction "1_1") (pintype "passive"))
      (node (ref "R51") (pin "2") (pinfunction "2_2") (pintype "passive"))
    )
    (net (code "59") (name "unconnected-(U15-BIAS-Pad17)") (class "Default")
      (node (ref "U15") (pin "17") (pinfunction "BIAS_17") (pintype "passive+no_connect"))
    )
    (net (code "60") (name "unconnected-(U15-NC-Pad9)") (class "Default")
      (node (ref "U15") (pin "9") (pinfunction "NC_9") (pintype "passive+no_connect"))
    )
    (net (code "61") (name "unconnected-(U15-NC-Pad12)") (class "Default")
      (node (ref "U15") (pin "12") (pinfunction "NC_12") (pintype "passive+no_connect"))
    )
    (net (code "62") (name "unconnected-(U15-PG-Pad18)") (class "Default")
      (node (ref "U15") (pin "18") (pinfunction "PG_18") (pintype "passive+no_connect"))
    )
    (net (code "63") (name "unconnected-(U21-~{FAULT}-Pad4)") (class "Default")
      (node (ref "U21") (pin "4") (pinfunction "~{FAULT}_4") (pintype "passive+no_connect"))
    )
  )
)
